# 40-auxiliary-backplane-board.net
KiCad netlist of a schematic drawn in EAGLE
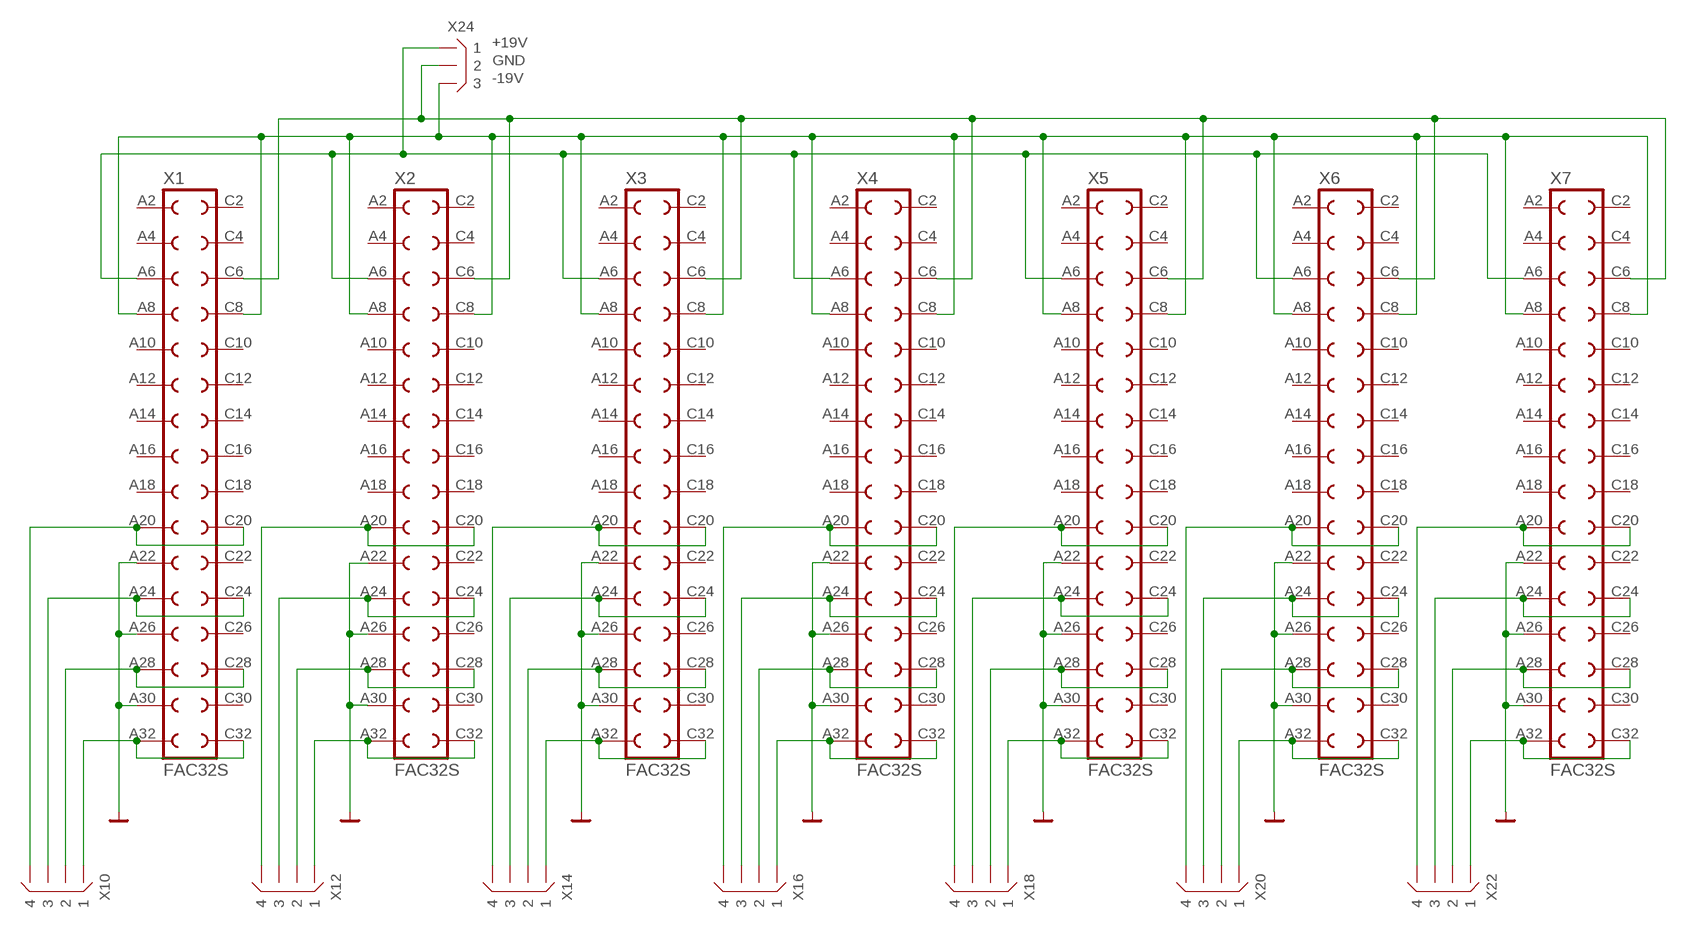
[diagram p0: schematic, sheet 1]

(export (version "E")
  (design (tool "Eeschema 10.0.6"))
  (components
    (comp (ref "X1")
      (value "FAC32S")
      (footprint "eagle-import:FAC32S")
      (libsource (lib "eagle-import") (part "FAC32S"))
    )
    (comp (ref "X2")
      (value "FAC32S")
      (footprint "eagle-import:FAC32S")
      (libsource (lib "eagle-import") (part "FAC32S"))
    )
    (comp (ref "X3")
      (value "FAC32S")
      (footprint "eagle-import:FAC32S")
      (libsource (lib "eagle-import") (part "FAC32S"))
    )
    (comp (ref "X4")
      (value "FAC32S")
      (footprint "eagle-import:FAC32S")
      (libsource (lib "eagle-import") (part "FAC32S"))
    )
    (comp (ref "X5")
      (value "FAC32S")
      (footprint "eagle-import:FAC32S")
      (libsource (lib "eagle-import") (part "FAC32S"))
    )
    (comp (ref "X6")
      (value "FAC32S")
      (footprint "eagle-import:FAC32S")
      (libsource (lib "eagle-import") (part "FAC32S"))
    )
    (comp (ref "X7")
      (value "FAC32S")
      (footprint "eagle-import:FAC32S")
      (libsource (lib "eagle-import") (part "FAC32S"))
    )
    (comp (ref "X10")
      (value "X04-SCREW")
      (footprint "eagle-import:X04-SCREW")
      (libsource (lib "eagle-import") (part "X04-SCREW"))
    )
    (comp (ref "X12")
      (value "X04-SCREW")
      (footprint "eagle-import:X04-SCREW")
      (libsource (lib "eagle-import") (part "X04-SCREW"))
    )
    (comp (ref "X14")
      (value "X04-SCREW")
      (footprint "eagle-import:X04-SCREW")
      (libsource (lib "eagle-import") (part "X04-SCREW"))
    )
    (comp (ref "X16")
      (value "X04-SCREW")
      (footprint "eagle-import:X04-SCREW")
      (libsource (lib "eagle-import") (part "X04-SCREW"))
    )
    (comp (ref "X18")
      (value "X04-SCREW")
      (footprint "eagle-import:X04-SCREW")
      (libsource (lib "eagle-import") (part "X04-SCREW"))
    )
    (comp (ref "X20")
      (value "X04-SCREW")
      (footprint "eagle-import:X04-SCREW")
      (libsource (lib "eagle-import") (part "X04-SCREW"))
    )
    (comp (ref "X22")
      (value "X04-SCREW")
      (footprint "eagle-import:X04-SCREW")
      (libsource (lib "eagle-import") (part "X04-SCREW"))
    )
    (comp (ref "X24")
      (value "X03-SCREW")
      (footprint "eagle-import:X03-SCREW")
      (libsource (lib "eagle-import") (part "X03-SCREW"))
    )
  )
  (nets
    (net (code "1") (name "Net-(X1-PadA6)") (class "Default")
      (node (ref "X1") (pin "A6") (pinfunction "A6_A6") (pintype "passive"))
      (node (ref "X2") (pin "A6") (pinfunction "A6_A6") (pintype "passive"))
      (node (ref "X24") (pin "1") (pinfunction "1_1") (pintype "bidirectional"))
      (node (ref "X3") (pin "A6") (pinfunction "A6_A6") (pintype "passive"))
      (node (ref "X4") (pin "A6") (pinfunction "A6_A6") (pintype "passive"))
      (node (ref "X5") (pin "A6") (pinfunction "A6_A6") (pintype "passive"))
      (node (ref "X6") (pin "A6") (pinfunction "A6_A6") (pintype "passive"))
      (node (ref "X7") (pin "A6") (pinfunction "A6_A6") (pintype "passive"))
    )
    (net (code "2") (name "Net-(X1-PadA8)") (class "Default")
      (node (ref "X1") (pin "A8") (pinfunction "A8_A8") (pintype "passive"))
      (node (ref "X1") (pin "C8") (pinfunction "C8_C8") (pintype "passive"))
      (node (ref "X2") (pin "A8") (pinfunction "A8_A8") (pintype "passive"))
      (node (ref "X2") (pin "C8") (pinfunction "C8_C8") (pintype "passive"))
      (node (ref "X24") (pin "3") (pinfunction "3_3") (pintype "bidirectional"))
      (node (ref "X3") (pin "A8") (pinfunction "A8_A8") (pintype "passive"))
      (node (ref "X3") (pin "C8") (pinfunction "C8_C8") (pintype "passive"))
      (node (ref "X4") (pin "A8") (pinfunction "A8_A8") (pintype "passive"))
      (node (ref "X4") (pin "C8") (pinfunction "C8_C8") (pintype "passive"))
      (node (ref "X5") (pin "A8") (pinfunction "A8_A8") (pintype "passive"))
      (node (ref "X5") (pin "C8") (pinfunction "C8_C8") (pintype "passive"))
      (node (ref "X6") (pin "A8") (pinfunction "A8_A8") (pintype "passive"))
      (node (ref "X6") (pin "C8") (pinfunction "C8_C8") (pintype "passive"))
      (node (ref "X7") (pin "A8") (pinfunction "A8_A8") (pintype "passive"))
      (node (ref "X7") (pin "C8") (pinfunction "C8_C8") (pintype "passive"))
    )
    (net (code "3") (name "Net-(X1-PadA20)") (class "Default")
      (node (ref "X1") (pin "A20") (pinfunction "A20_A20") (pintype "passive"))
      (node (ref "X1") (pin "C20") (pinfunction "C20_C20") (pintype "passive"))
      (node (ref "X10") (pin "4") (pinfunction "4_4") (pintype "bidirectional"))
    )
    (net (code "4") (name "Net-(X1-PadA24)") (class "Default")
      (node (ref "X1") (pin "A24") (pinfunction "A24_A24") (pintype "passive"))
      (node (ref "X1") (pin "C24") (pinfunction "C24_C24") (pintype "passive"))
      (node (ref "X10") (pin "3") (pinfunction "3_3") (pintype "bidirectional"))
    )
    (net (code "5") (name "Net-(X1-PadA28)") (class "Default")
      (node (ref "X1") (pin "A28") (pinfunction "A28_A28") (pintype "passive"))
      (node (ref "X1") (pin "C28") (pinfunction "C28_C28") (pintype "passive"))
      (node (ref "X10") (pin "2") (pinfunction "2_2") (pintype "bidirectional"))
    )
    (net (code "6") (name "Net-(X1-PadA32)") (class "Default")
      (node (ref "X1") (pin "A32") (pinfunction "A32_A32") (pintype "passive"))
      (node (ref "X1") (pin "C32") (pinfunction "C32_C32") (pintype "passive"))
      (node (ref "X10") (pin "1") (pinfunction "1_1") (pintype "bidirectional"))
    )
    (net (code "7") (name "Net-(X1-PadC6)") (class "Default")
      (node (ref "X1") (pin "C6") (pinfunction "C6_C6") (pintype "passive"))
      (node (ref "X2") (pin "C6") (pinfunction "C6_C6") (pintype "passive"))
      (node (ref "X24") (pin "2") (pinfunction "2_2") (pintype "bidirectional"))
      (node (ref "X3") (pin "C6") (pinfunction "C6_C6") (pintype "passive"))
      (node (ref "X4") (pin "C6") (pinfunction "C6_C6") (pintype "passive"))
      (node (ref "X5") (pin "C6") (pinfunction "C6_C6") (pintype "passive"))
      (node (ref "X6") (pin "C6") (pinfunction "C6_C6") (pintype "passive"))
      (node (ref "X7") (pin "C6") (pinfunction "C6_C6") (pintype "passive"))
    )
    (net (code "8") (name "Net-(X12-Pad1)") (class "Default")
      (node (ref "X12") (pin "1") (pinfunction "1_1") (pintype "bidirectional"))
      (node (ref "X2") (pin "A32") (pinfunction "A32_A32") (pintype "passive"))
      (node (ref "X2") (pin "C32") (pinfunction "C32_C32") (pintype "passive"))
    )
    (net (code "9") (name "Net-(X12-Pad2)") (class "Default")
      (node (ref "X12") (pin "2") (pinfunction "2_2") (pintype "bidirectional"))
      (node (ref "X2") (pin "A28") (pinfunction "A28_A28") (pintype "passive"))
      (node (ref "X2") (pin "C28") (pinfunction "C28_C28") (pintype "passive"))
    )
    (net (code "10") (name "Net-(X12-Pad3)") (class "Default")
      (node (ref "X12") (pin "3") (pinfunction "3_3") (pintype "bidirectional"))
      (node (ref "X2") (pin "A24") (pinfunction "A24_A24") (pintype "passive"))
      (node (ref "X2") (pin "C24") (pinfunction "C24_C24") (pintype "passive"))
    )
    (net (code "11") (name "Net-(X12-Pad4)") (class "Default")
      (node (ref "X12") (pin "4") (pinfunction "4_4") (pintype "bidirectional"))
      (node (ref "X2") (pin "A20") (pinfunction "A20_A20") (pintype "passive"))
      (node (ref "X2") (pin "C20") (pinfunction "C20_C20") (pintype "passive"))
    )
    (net (code "12") (name "Net-(X14-Pad1)") (class "Default")
      (node (ref "X14") (pin "1") (pinfunction "1_1") (pintype "bidirectional"))
      (node (ref "X3") (pin "A32") (pinfunction "A32_A32") (pintype "passive"))
      (node (ref "X3") (pin "C32") (pinfunction "C32_C32") (pintype "passive"))
    )
    (net (code "13") (name "Net-(X14-Pad2)") (class "Default")
      (node (ref "X14") (pin "2") (pinfunction "2_2") (pintype "bidirectional"))
      (node (ref "X3") (pin "A28") (pinfunction "A28_A28") (pintype "passive"))
      (node (ref "X3") (pin "C28") (pinfunction "C28_C28") (pintype "passive"))
    )
    (net (code "14") (name "Net-(X14-Pad3)") (class "Default")
      (node (ref "X14") (pin "3") (pinfunction "3_3") (pintype "bidirectional"))
      (node (ref "X3") (pin "A24") (pinfunction "A24_A24") (pintype "passive"))
      (node (ref "X3") (pin "C24") (pinfunction "C24_C24") (pintype "passive"))
    )
    (net (code "15") (name "Net-(X14-Pad4)") (class "Default")
      (node (ref "X14") (pin "4") (pinfunction "4_4") (pintype "bidirectional"))
      (node (ref "X3") (pin "A20") (pinfunction "A20_A20") (pintype "passive"))
      (node (ref "X3") (pin "C20") (pinfunction "C20_C20") (pintype "passive"))
    )
    (net (code "16") (name "Net-(X16-Pad1)") (class "Default")
      (node (ref "X16") (pin "1") (pinfunction "1_1") (pintype "bidirectional"))
      (node (ref "X4") (pin "A32") (pinfunction "A32_A32") (pintype "passive"))
      (node (ref "X4") (pin "C32") (pinfunction "C32_C32") (pintype "passive"))
    )
    (net (code "17") (name "Net-(X16-Pad2)") (class "Default")
      (node (ref "X16") (pin "2") (pinfunction "2_2") (pintype "bidirectional"))
      (node (ref "X4") (pin "A28") (pinfunction "A28_A28") (pintype "passive"))
      (node (ref "X4") (pin "C28") (pinfunction "C28_C28") (pintype "passive"))
    )
    (net (code "18") (name "Net-(X16-Pad3)") (class "Default")
      (node (ref "X16") (pin "3") (pinfunction "3_3") (pintype "bidirectional"))
      (node (ref "X4") (pin "A24") (pinfunction "A24_A24") (pintype "passive"))
      (node (ref "X4") (pin "C24") (pinfunction "C24_C24") (pintype "passive"))
    )
    (net (code "19") (name "Net-(X16-Pad4)") (class "Default")
      (node (ref "X16") (pin "4") (pinfunction "4_4") (pintype "bidirectional"))
      (node (ref "X4") (pin "A20") (pinfunction "A20_A20") (pintype "passive"))
      (node (ref "X4") (pin "C20") (pinfunction "C20_C20") (pintype "passive"))
    )
    (net (code "20") (name "Net-(X18-Pad1)") (class "Default")
      (node (ref "X18") (pin "1") (pinfunction "1_1") (pintype "bidirectional"))
      (node (ref "X5") (pin "A32") (pinfunction "A32_A32") (pintype "passive"))
      (node (ref "X5") (pin "C32") (pinfunction "C32_C32") (pintype "passive"))
    )
    (net (code "21") (name "Net-(X18-Pad2)") (class "Default")
      (node (ref "X18") (pin "2") (pinfunction "2_2") (pintype "bidirectional"))
      (node (ref "X5") (pin "A28") (pinfunction "A28_A28") (pintype "passive"))
      (node (ref "X5") (pin "C28") (pinfunction "C28_C28") (pintype "passive"))
    )
    (net (code "22") (name "Net-(X18-Pad3)") (class "Default")
      (node (ref "X18") (pin "3") (pinfunction "3_3") (pintype "bidirectional"))
      (node (ref "X5") (pin "A24") (pinfunction "A24_A24") (pintype "passive"))
      (node (ref "X5") (pin "C24") (pinfunction "C24_C24") (pintype "passive"))
    )
    (net (code "23") (name "Net-(X18-Pad4)") (class "Default")
      (node (ref "X18") (pin "4") (pinfunction "4_4") (pintype "bidirectional"))
      (node (ref "X5") (pin "A20") (pinfunction "A20_A20") (pintype "passive"))
      (node (ref "X5") (pin "C20") (pinfunction "C20_C20") (pintype "passive"))
    )
    (net (code "24") (name "Net-(X20-Pad1)") (class "Default")
      (node (ref "X20") (pin "1") (pinfunction "1_1") (pintype "bidirectional"))
      (node (ref "X6") (pin "A32") (pinfunction "A32_A32") (pintype "passive"))
      (node (ref "X6") (pin "C32") (pinfunction "C32_C32") (pintype "passive"))
    )
    (net (code "25") (name "Net-(X20-Pad2)") (class "Default")
      (node (ref "X20") (pin "2") (pinfunction "2_2") (pintype "bidirectional"))
      (node (ref "X6") (pin "A28") (pinfunction "A28_A28") (pintype "passive"))
      (node (ref "X6") (pin "C28") (pinfunction "C28_C28") (pintype "passive"))
    )
    (net (code "26") (name "Net-(X20-Pad3)") (class "Default")
      (node (ref "X20") (pin "3") (pinfunction "3_3") (pintype "bidirectional"))
      (node (ref "X6") (pin "A24") (pinfunction "A24_A24") (pintype "passive"))
      (node (ref "X6") (pin "C24") (pinfunction "C24_C24") (pintype "passive"))
    )
    (net (code "27") (name "Net-(X20-Pad4)") (class "Default")
      (node (ref "X20") (pin "4") (pinfunction "4_4") (pintype "bidirectional"))
      (node (ref "X6") (pin "A20") (pinfunction "A20_A20") (pintype "passive"))
      (node (ref "X6") (pin "C20") (pinfunction "C20_C20") (pintype "passive"))
    )
    (net (code "28") (name "Net-(X22-Pad1)") (class "Default")
      (node (ref "X22") (pin "1") (pinfunction "1_1") (pintype "bidirectional"))
      (node (ref "X7") (pin "A32") (pinfunction "A32_A32") (pintype "passive"))
      (node (ref "X7") (pin "C32") (pinfunction "C32_C32") (pintype "passive"))
    )
    (net (code "29") (name "Net-(X22-Pad2)") (class "Default")
      (node (ref "X22") (pin "2") (pinfunction "2_2") (pintype "bidirectional"))
      (node (ref "X7") (pin "A28") (pinfunction "A28_A28") (pintype "passive"))
      (node (ref "X7") (pin "C28") (pinfunction "C28_C28") (pintype "passive"))
    )
    (net (code "30") (name "Net-(X22-Pad3)") (class "Default")
      (node (ref "X22") (pin "3") (pinfunction "3_3") (pintype "bidirectional"))
      (node (ref "X7") (pin "A24") (pinfunction "A24_A24") (pintype "passive"))
      (node (ref "X7") (pin "C24") (pinfunction "C24_C24") (pintype "passive"))
    )
    (net (code "31") (name "Net-(X22-Pad4)") (class "Default")
      (node (ref "X22") (pin "4") (pinfunction "4_4") (pintype "bidirectional"))
      (node (ref "X7") (pin "A20") (pinfunction "A20_A20") (pintype "passive"))
      (node (ref "X7") (pin "C20") (pinfunction "C20_C20") (pintype "passive"))
    )
    (net (code "32") (name "VG") (class "Default")
      (node (ref "X1") (pin "A22") (pinfunction "A22_A22") (pintype "passive"))
      (node (ref "X1") (pin "A26") (pinfunction "A26_A26") (pintype "passive"))
      (node (ref "X1") (pin "A30") (pinfunction "A30_A30") (pintype "passive"))
      (node (ref "X2") (pin "A22") (pinfunction "A22_A22") (pintype "passive"))
      (node (ref "X2") (pin "A26") (pinfunction "A26_A26") (pintype "passive"))
      (node (ref "X2") (pin "A30") (pinfunction "A30_A30") (pintype "passive"))
      (node (ref "X3") (pin "A22") (pinfunction "A22_A22") (pintype "passive"))
      (node (ref "X3") (pin "A26") (pinfunction "A26_A26") (pintype "passive"))
      (node (ref "X3") (pin "A30") (pinfunction "A30_A30") (pintype "passive"))
      (node (ref "X4") (pin "A22") (pinfunction "A22_A22") (pintype "passive"))
      (node (ref "X4") (pin "A26") (pinfunction "A26_A26") (pintype "passive"))
      (node (ref "X4") (pin "A30") (pinfunction "A30_A30") (pintype "passive"))
      (node (ref "X5") (pin "A22") (pinfunction "A22_A22") (pintype "passive"))
      (node (ref "X5") (pin "A26") (pinfunction "A26_A26") (pintype "passive"))
      (node (ref "X5") (pin "A30") (pinfunction "A30_A30") (pintype "passive"))
      (node (ref "X6") (pin "A22") (pinfunction "A22_A22") (pintype "passive"))
      (node (ref "X6") (pin "A26") (pinfunction "A26_A26") (pintype "passive"))
      (node (ref "X6") (pin "A30") (pinfunction "A30_A30") (pintype "passive"))
      (node (ref "X7") (pin "A22") (pinfunction "A22_A22") (pintype "passive"))
      (node (ref "X7") (pin "A26") (pinfunction "A26_A26") (pintype "passive"))
      (node (ref "X7") (pin "A30") (pinfunction "A30_A30") (pintype "passive"))
    )
    (net (code "33") (name "unconnected-(X1-PadA2)") (class "Default")
      (node (ref "X1") (pin "A2") (pinfunction "A2_A2") (pintype "passive"))
    )
    (net (code "34") (name "unconnected-(X1-PadA4)") (class "Default")
      (node (ref "X1") (pin "A4") (pinfunction "A4_A4") (pintype "passive"))
    )
    (net (code "35") (name "unconnected-(X1-PadA10)") (class "Default")
      (node (ref "X1") (pin "A10") (pinfunction "A10_A10") (pintype "passive"))
    )
    (net (code "36") (name "unconnected-(X1-PadA12)") (class "Default")
      (node (ref "X1") (pin "A12") (pinfunction "A12_A12") (pintype "passive"))
    )
    (net (code "37") (name "unconnected-(X1-PadA14)") (class "Default")
      (node (ref "X1") (pin "A14") (pinfunction "A14_A14") (pintype "passive"))
    )
    (net (code "38") (name "unconnected-(X1-PadA16)") (class "Default")
      (node (ref "X1") (pin "A16") (pinfunction "A16_A16") (pintype "passive"))
    )
    (net (code "39") (name "unconnected-(X1-PadA18)") (class "Default")
      (node (ref "X1") (pin "A18") (pinfunction "A18_A18") (pintype "passive"))
    )
    (net (code "40") (name "unconnected-(X1-PadC2)") (class "Default")
      (node (ref "X1") (pin "C2") (pinfunction "C2_C2") (pintype "passive"))
    )
    (net (code "41") (name "unconnected-(X1-PadC4)") (class "Default")
      (node (ref "X1") (pin "C4") (pinfunction "C4_C4") (pintype "passive"))
    )
    (net (code "42") (name "unconnected-(X1-PadC10)") (class "Default")
      (node (ref "X1") (pin "C10") (pinfunction "C10_C10") (pintype "passive"))
    )
    (net (code "43") (name "unconnected-(X1-PadC12)") (class "Default")
      (node (ref "X1") (pin "C12") (pinfunction "C12_C12") (pintype "passive"))
    )
    (net (code "44") (name "unconnected-(X1-PadC14)") (class "Default")
      (node (ref "X1") (pin "C14") (pinfunction "C14_C14") (pintype "passive"))
    )
    (net (code "45") (name "unconnected-(X1-PadC16)") (class "Default")
      (node (ref "X1") (pin "C16") (pinfunction "C16_C16") (pintype "passive"))
    )
    (net (code "46") (name "unconnected-(X1-PadC18)") (class "Default")
      (node (ref "X1") (pin "C18") (pinfunction "C18_C18") (pintype "passive"))
    )
    (net (code "47") (name "unconnected-(X1-PadC22)") (class "Default")
      (node (ref "X1") (pin "C22") (pinfunction "C22_C22") (pintype "passive"))
    )
    (net (code "48") (name "unconnected-(X1-PadC26)") (class "Default")
      (node (ref "X1") (pin "C26") (pinfunction "C26_C26") (pintype "passive"))
    )
    (net (code "49") (name "unconnected-(X1-PadC30)") (class "Default")
      (node (ref "X1") (pin "C30") (pinfunction "C30_C30") (pintype "passive"))
    )
    (net (code "50") (name "unconnected-(X2-PadA2)") (class "Default")
      (node (ref "X2") (pin "A2") (pinfunction "A2_A2") (pintype "passive"))
    )
    (net (code "51") (name "unconnected-(X2-PadA4)") (class "Default")
      (node (ref "X2") (pin "A4") (pinfunction "A4_A4") (pintype "passive"))
    )
    (net (code "52") (name "unconnected-(X2-PadA10)") (class "Default")
      (node (ref "X2") (pin "A10") (pinfunction "A10_A10") (pintype "passive"))
    )
    (net (code "53") (name "unconnected-(X2-PadA12)") (class "Default")
      (node (ref "X2") (pin "A12") (pinfunction "A12_A12") (pintype "passive"))
    )
    (net (code "54") (name "unconnected-(X2-PadA14)") (class "Default")
      (node (ref "X2") (pin "A14") (pinfunction "A14_A14") (pintype "passive"))
    )
    (net (code "55") (name "unconnected-(X2-PadA16)") (class "Default")
      (node (ref "X2") (pin "A16") (pinfunction "A16_A16") (pintype "passive"))
    )
    (net (code "56") (name "unconnected-(X2-PadA18)") (class "Default")
      (node (ref "X2") (pin "A18") (pinfunction "A18_A18") (pintype "passive"))
    )
    (net (code "57") (name "unconnected-(X2-PadC2)") (class "Default")
      (node (ref "X2") (pin "C2") (pinfunction "C2_C2") (pintype "passive"))
    )
    (net (code "58") (name "unconnected-(X2-PadC4)") (class "Default")
      (node (ref "X2") (pin "C4") (pinfunction "C4_C4") (pintype "passive"))
    )
    (net (code "59") (name "unconnected-(X2-PadC10)") (class "Default")
      (node (ref "X2") (pin "C10") (pinfunction "C10_C10") (pintype "passive"))
    )
    (net (code "60") (name "unconnected-(X2-PadC12)") (class "Default")
      (node (ref "X2") (pin "C12") (pinfunction "C12_C12") (pintype "passive"))
    )
    (net (code "61") (name "unconnected-(X2-PadC14)") (class "Default")
      (node (ref "X2") (pin "C14") (pinfunction "C14_C14") (pintype "passive"))
    )
    (net (code "62") (name "unconnected-(X2-PadC16)") (class "Default")
      (node (ref "X2") (pin "C16") (pinfunction "C16_C16") (pintype "passive"))
    )
    (net (code "63") (name "unconnected-(X2-PadC18)") (class "Default")
      (node (ref "X2") (pin "C18") (pinfunction "C18_C18") (pintype "passive"))
    )
    (net (code "64") (name "unconnected-(X2-PadC22)") (class "Default")
      (node (ref "X2") (pin "C22") (pinfunction "C22_C22") (pintype "passive"))
    )
    (net (code "65") (name "unconnected-(X2-PadC26)") (class "Default")
      (node (ref "X2") (pin "C26") (pinfunction "C26_C26") (pintype "passive"))
    )
    (net (code "66") (name "unconnected-(X2-PadC30)") (class "Default")
      (node (ref "X2") (pin "C30") (pinfunction "C30_C30") (pintype "passive"))
    )
    (net (code "67") (name "unconnected-(X3-PadA2)") (class "Default")
      (node (ref "X3") (pin "A2") (pinfunction "A2_A2") (pintype "passive"))
    )
    (net (code "68") (name "unconnected-(X3-PadA4)") (class "Default")
      (node (ref "X3") (pin "A4") (pinfunction "A4_A4") (pintype "passive"))
    )
    (net (code "69") (name "unconnected-(X3-PadA10)") (class "Default")
      (node (ref "X3") (pin "A10") (pinfunction "A10_A10") (pintype "passive"))
    )
    (net (code "70") (name "unconnected-(X3-PadA12)") (class "Default")
      (node (ref "X3") (pin "A12") (pinfunction "A12_A12") (pintype "passive"))
    )
    (net (code "71") (name "unconnected-(X3-PadA14)") (class "Default")
      (node (ref "X3") (pin "A14") (pinfunction "A14_A14") (pintype "passive"))
    )
    (net (code "72") (name "unconnected-(X3-PadA16)") (class "Default")
      (node (ref "X3") (pin "A16") (pinfunction "A16_A16") (pintype "passive"))
    )
    (net (code "73") (name "unconnected-(X3-PadA18)") (class "Default")
      (node (ref "X3") (pin "A18") (pinfunction "A18_A18") (pintype "passive"))
    )
    (net (code "74") (name "unconnected-(X3-PadC2)") (class "Default")
      (node (ref "X3") (pin "C2") (pinfunction "C2_C2") (pintype "passive"))
    )
    (net (code "75") (name "unconnected-(X3-PadC4)") (class "Default")
      (node (ref "X3") (pin "C4") (pinfunction "C4_C4") (pintype "passive"))
    )
    (net (code "76") (name "unconnected-(X3-PadC10)") (class "Default")
      (node (ref "X3") (pin "C10") (pinfunction "C10_C10") (pintype "passive"))
    )
    (net (code "77") (name "unconnected-(X3-PadC12)") (class "Default")
      (node (ref "X3") (pin "C12") (pinfunction "C12_C12") (pintype "passive"))
    )
    (net (code "78") (name "unconnected-(X3-PadC14)") (class "Default")
      (node (ref "X3") (pin "C14") (pinfunction "C14_C14") (pintype "passive"))
    )
    (net (code "79") (name "unconnected-(X3-PadC16)") (class "Default")
      (node (ref "X3") (pin "C16") (pinfunction "C16_C16") (pintype "passive"))
    )
    (net (code "80") (name "unconnected-(X3-PadC18)") (class "Default")
      (node (ref "X3") (pin "C18") (pinfunction "C18_C18") (pintype "passive"))
    )
    (net (code "81") (name "unconnected-(X3-PadC22)") (class "Default")
      (node (ref "X3") (pin "C22") (pinfunction "C22_C22") (pintype "passive"))
    )
    (net (code "82") (name "unconnected-(X3-PadC26)") (class "Default")
      (node (ref "X3") (pin "C26") (pinfunction "C26_C26") (pintype "passive"))
    )
    (net (code "83") (name "unconnected-(X3-PadC30)") (class "Default")
      (node (ref "X3") (pin "C30") (pinfunction "C30_C30") (pintype "passive"))
    )
    (net (code "84") (name "unconnected-(X4-PadA2)") (class "Default")
      (node (ref "X4") (pin "A2") (pinfunction "A2_A2") (pintype "passive"))
    )
    (net (code "85") (name "unconnected-(X4-PadA4)") (class "Default")
      (node (ref "X4") (pin "A4") (pinfunction "A4_A4") (pintype "passive"))
    )
    (net (code "86") (name "unconnected-(X4-PadA10)") (class "Default")
      (node (ref "X4") (pin "A10") (pinfunction "A10_A10") (pintype "passive"))
    )
    (net (code "87") (name "unconnected-(X4-PadA12)") (class "Default")
      (node (ref "X4") (pin "A12") (pinfunction "A12_A12") (pintype "passive"))
    )
    (net (code "88") (name "unconnected-(X4-PadA14)") (class "Default")
      (node (ref "X4") (pin "A14") (pinfunction "A14_A14") (pintype "passive"))
    )
    (net (code "89") (name "unconnected-(X4-PadA16)") (class "Default")
      (node (ref "X4") (pin "A16") (pinfunction "A16_A16") (pintype "passive"))
    )
    (net (code "90") (name "unconnected-(X4-PadA18)") (class "Default")
      (node (ref "X4") (pin "A18") (pinfunction "A18_A18") (pintype "passive"))
    )
    (net (code "91") (name "unconnected-(X4-PadC2)") (class "Default")
      (node (ref "X4") (pin "C2") (pinfunction "C2_C2") (pintype "passive"))
    )
    (net (code "92") (name "unconnected-(X4-PadC4)") (class "Default")
      (node (ref "X4") (pin "C4") (pinfunction "C4_C4") (pintype "passive"))
    )
    (net (code "93") (name "unconnected-(X4-PadC10)") (class "Default")
      (node (ref "X4") (pin "C10") (pinfunction "C10_C10") (pintype "passive"))
    )
    (net (code "94") (name "unconnected-(X4-PadC12)") (class "Default")
      (node (ref "X4") (pin "C12") (pinfunction "C12_C12") (pintype "passive"))
    )
    (net (code "95") (name "unconnected-(X4-PadC14)") (class "Default")
      (node (ref "X4") (pin "C14") (pinfunction "C14_C14") (pintype "passive"))
    )
    (net (code "96") (name "unconnected-(X4-PadC16)") (class "Default")
      (node (ref "X4") (pin "C16") (pinfunction "C16_C16") (pintype "passive"))
    )
    (net (code "97") (name "unconnected-(X4-PadC18)") (class "Default")
      (node (ref "X4") (pin "C18") (pinfunction "C18_C18") (pintype "passive"))
    )
    (net (code "98") (name "unconnected-(X4-PadC22)") (class "Default")
      (node (ref "X4") (pin "C22") (pinfunction "C22_C22") (pintype "passive"))
    )
    (net (code "99") (name "unconnected-(X4-PadC26)") (class "Default")
      (node (ref "X4") (pin "C26") (pinfunction "C26_C26") (pintype "passive"))
    )
    (net (code "100") (name "unconnected-(X4-PadC30)") (class "Default")
      (node (ref "X4") (pin "C30") (pinfunction "C30_C30") (pintype "passive"))
    )
    (net (code "101") (name "unconnected-(X5-PadA2)") (class "Default")
      (node (ref "X5") (pin "A2") (pinfunction "A2_A2") (pintype "passive"))
    )
    (net (code "102") (name "unconnected-(X5-PadA4)") (class "Default")
      (node (ref "X5") (pin "A4") (pinfunction "A4_A4") (pintype "passive"))
    )
    (net (code "103") (name "unconnected-(X5-PadA10)") (class "Default")
      (node (ref "X5") (pin "A10") (pinfunction "A10_A10") (pintype "passive"))
    )
    (net (code "104") (name "unconnected-(X5-PadA12)") (class "Default")
      (node (ref "X5") (pin "A12") (pinfunction "A12_A12") (pintype "passive"))
    )
    (net (code "105") (name "unconnected-(X5-PadA14)") (class "Default")
      (node (ref "X5") (pin "A14") (pinfunction "A14_A14") (pintype "passive"))
    )
    (net (code "106") (name "unconnected-(X5-PadA16)") (class "Default")
      (node (ref "X5") (pin "A16") (pinfunction "A16_A16") (pintype "passive"))
    )
    (net (code "107") (name "unconnected-(X5-PadA18)") (class "Default")
      (node (ref "X5") (pin "A18") (pinfunction "A18_A18") (pintype "passive"))
    )
    (net (code "108") (name "unconnected-(X5-PadC2)") (class "Default")
      (node (ref "X5") (pin "C2") (pinfunction "C2_C2") (pintype "passive"))
    )
    (net (code "109") (name "unconnected-(X5-PadC4)") (class "Default")
      (node (ref "X5") (pin "C4") (pinfunction "C4_C4") (pintype "passive"))
    )
    (net (code "110") (name "unconnected-(X5-PadC10)") (class "Default")
      (node (ref "X5") (pin "C10") (pinfunction "C10_C10") (pintype "passive"))
    )
    (net (code "111") (name "unconnected-(X5-PadC12)") (class "Default")
      (node (ref "X5") (pin "C12") (pinfunction "C12_C12") (pintype "passive"))
    )
    (net (code "112") (name "unconnected-(X5-PadC14)") (class "Default")
      (node (ref "X5") (pin "C14") (pinfunction "C14_C14") (pintype "passive"))
    )
    (net (code "113") (name "unconnected-(X5-PadC16)") (class "Default")
      (node (ref "X5") (pin "C16") (pinfunction "C16_C16") (pintype "passive"))
    )
    (net (code "114") (name "unconnected-(X5-PadC18)") (class "Default")
      (node (ref "X5") (pin "C18") (pinfunction "C18_C18") (pintype "passive"))
    )
    (net (code "115") (name "unconnected-(X5-PadC22)") (class "Default")
      (node (ref "X5") (pin "C22") (pinfunction "C22_C22") (pintype "passive"))
    )
    (net (code "116") (name "unconnected-(X5-PadC26)") (class "Default")
      (node (ref "X5") (pin "C26") (pinfunction "C26_C26") (pintype "passive"))
    )
    (net (code "117") (name "unconnected-(X5-PadC30)") (class "Default")
      (node (ref "X5") (pin "C30") (pinfunction "C30_C30") (pintype "passive"))
    )
    (net (code "118") (name "unconnected-(X6-PadA2)") (class "Default")
      (node (ref "X6") (pin "A2") (pinfunction "A2_A2") (pintype "passive"))
    )
    (net (code "119") (name "unconnected-(X6-PadA4)") (class "Default")
      (node (ref "X6") (pin "A4") (pinfunction "A4_A4") (pintype "passive"))
    )
    (net (code "120") (name "unconnected-(X6-PadA10)") (class "Default")
      (node (ref "X6") (pin "A10") (pinfunction "A10_A10") (pintype "passive"))
    )
    (net (code "121") (name "unconnected-(X6-PadA12)") (class "Default")
      (node (ref "X6") (pin "A12") (pinfunction "A12_A12") (pintype "passive"))
    )
    (net (code "122") (name "unconnected-(X6-PadA14)") (class "Default")
      (node (ref "X6") (pin "A14") (pinfunction "A14_A14") (pintype "passive"))
    )
    (net (code "123") (name "unconnected-(X6-PadA16)") (class "Default")
      (node (ref "X6") (pin "A16") (pinfunction "A16_A16") (pintype "passive"))
    )
    (net (code "124") (name "unconnected-(X6-PadA18)") (class "Default")
      (node (ref "X6") (pin "A18") (pinfunction "A18_A18") (pintype "passive"))
    )
    (net (code "125") (name "unconnected-(X6-PadC2)") (class "Default")
      (node (ref "X6") (pin "C2") (pinfunction "C2_C2") (pintype "passive"))
    )
    (net (code "126") (name "unconnected-(X6-PadC4)") (class "Default")
      (node (ref "X6") (pin "C4") (pinfunction "C4_C4") (pintype "passive"))
    )
    (net (code "127") (name "unconnected-(X6-PadC10)") (class "Default")
      (node (ref "X6") (pin "C10") (pinfunction "C10_C10") (pintype "passive"))
    )
    (net (code "128") (name "unconnected-(X6-PadC12)") (class "Default")
      (node (ref "X6") (pin "C12") (pinfunction "C12_C12") (pintype "passive"))
    )
    (net (code "129") (name "unconnected-(X6-PadC14)") (class "Default")
      (node (ref "X6") (pin "C14") (pinfunction "C14_C14") (pintype "passive"))
    )
    (net (code "130") (name "unconnected-(X6-PadC16)") (class "Default")
      (node (ref "X6") (pin "C16") (pinfunction "C16_C16") (pintype "passive"))
    )
    (net (code "131") (name "unconnected-(X6-PadC18)") (class "Default")
      (node (ref "X6") (pin "C18") (pinfunction "C18_C18") (pintype "passive"))
    )
    (net (code "132") (name "unconnected-(X6-PadC22)") (class "Default")
      (node (ref "X6") (pin "C22") (pinfunction "C22_C22") (pintype "passive"))
    )
    (net (code "133") (name "unconnected-(X6-PadC26)") (class "Default")
      (node (ref "X6") (pin "C26") (pinfunction "C26_C26") (pintype "passive"))
    )
    (net (code "134") (name "unconnected-(X6-PadC30)") (class "Default")
      (node (ref "X6") (pin "C30") (pinfunction "C30_C30") (pintype "passive"))
    )
    (net (code "135") (name "unconnected-(X7-PadA2)") (class "Default")
      (node (ref "X7") (pin "A2") (pinfunction "A2_A2") (pintype "passive"))
    )
    (net (code "136") (name "unconnected-(X7-PadA4)") (class "Default")
      (node (ref "X7") (pin "A4") (pinfunction "A4_A4") (pintype "passive"))
    )
    (net (code "137") (name "unconnected-(X7-PadA10)") (class "Default")
      (node (ref "X7") (pin "A10") (pinfunction "A10_A10") (pintype "passive"))
    )
    (net (code "138") (name "unconnected-(X7-PadA12)") (class "Default")
      (node (ref "X7") (pin "A12") (pinfunction "A12_A12") (pintype "passive"))
    )
    (net (code "139") (name "unconnected-(X7-PadA14)") (class "Default")
      (node (ref "X7") (pin "A14") (pinfunction "A14_A14") (pintype "passive"))
    )
    (net (code "140") (name "unconnected-(X7-PadA16)") (class "Default")
      (node (ref "X7") (pin "A16") (pinfunction "A16_A16") (pintype "passive"))
    )
    (net (code "141") (name "unconnected-(X7-PadA18)") (class "Default")
      (node (ref "X7") (pin "A18") (pinfunction "A18_A18") (pintype "passive"))
    )
    (net (code "142") (name "unconnected-(X7-PadC2)") (class "Default")
      (node (ref "X7") (pin "C2") (pinfunction "C2_C2") (pintype "passive"))
    )
    (net (code "143") (name "unconnected-(X7-PadC4)") (class "Default")
      (node (ref "X7") (pin "C4") (pinfunction "C4_C4") (pintype "passive"))
    )
    (net (code "144") (name "unconnected-(X7-PadC10)") (class "Default")
      (node (ref "X7") (pin "C10") (pinfunction "C10_C10") (pintype "passive"))
    )
    (net (code "145") (name "unconnected-(X7-PadC12)") (class "Default")
      (node (ref "X7") (pin "C12") (pinfunction "C12_C12") (pintype "passive"))
    )
    (net (code "146") (name "unconnected-(X7-PadC14)") (class "Default")
      (node (ref "X7") (pin "C14") (pinfunction "C14_C14") (pintype "passive"))
    )
    (net (code "147") (name "unconnected-(X7-PadC16)") (class "Default")
      (node (ref "X7") (pin "C16") (pinfunction "C16_C16") (pintype "passive"))
    )
    (net (code "148") (name "unconnected-(X7-PadC18)") (class "Default")
      (node (ref "X7") (pin "C18") (pinfunction "C18_C18") (pintype "passive"))
    )
    (net (code "149") (name "unconnected-(X7-PadC22)") (class "Default")
      (node (ref "X7") (pin "C22") (pinfunction "C22_C22") (pintype "passive"))
    )
    (net (code "150") (name "unconnected-(X7-PadC26)") (class "Default")
      (node (ref "X7") (pin "C26") (pinfunction "C26_C26") (pintype "passive"))
    )
    (net (code "151") (name "unconnected-(X7-PadC30)") (class "Default")
      (node (ref "X7") (pin "C30") (pinfunction "C30_C30") (pintype "passive"))
    )
  )
)
